# SENSING.net
KiCad netlist of a schematic drawn in Altium Designer
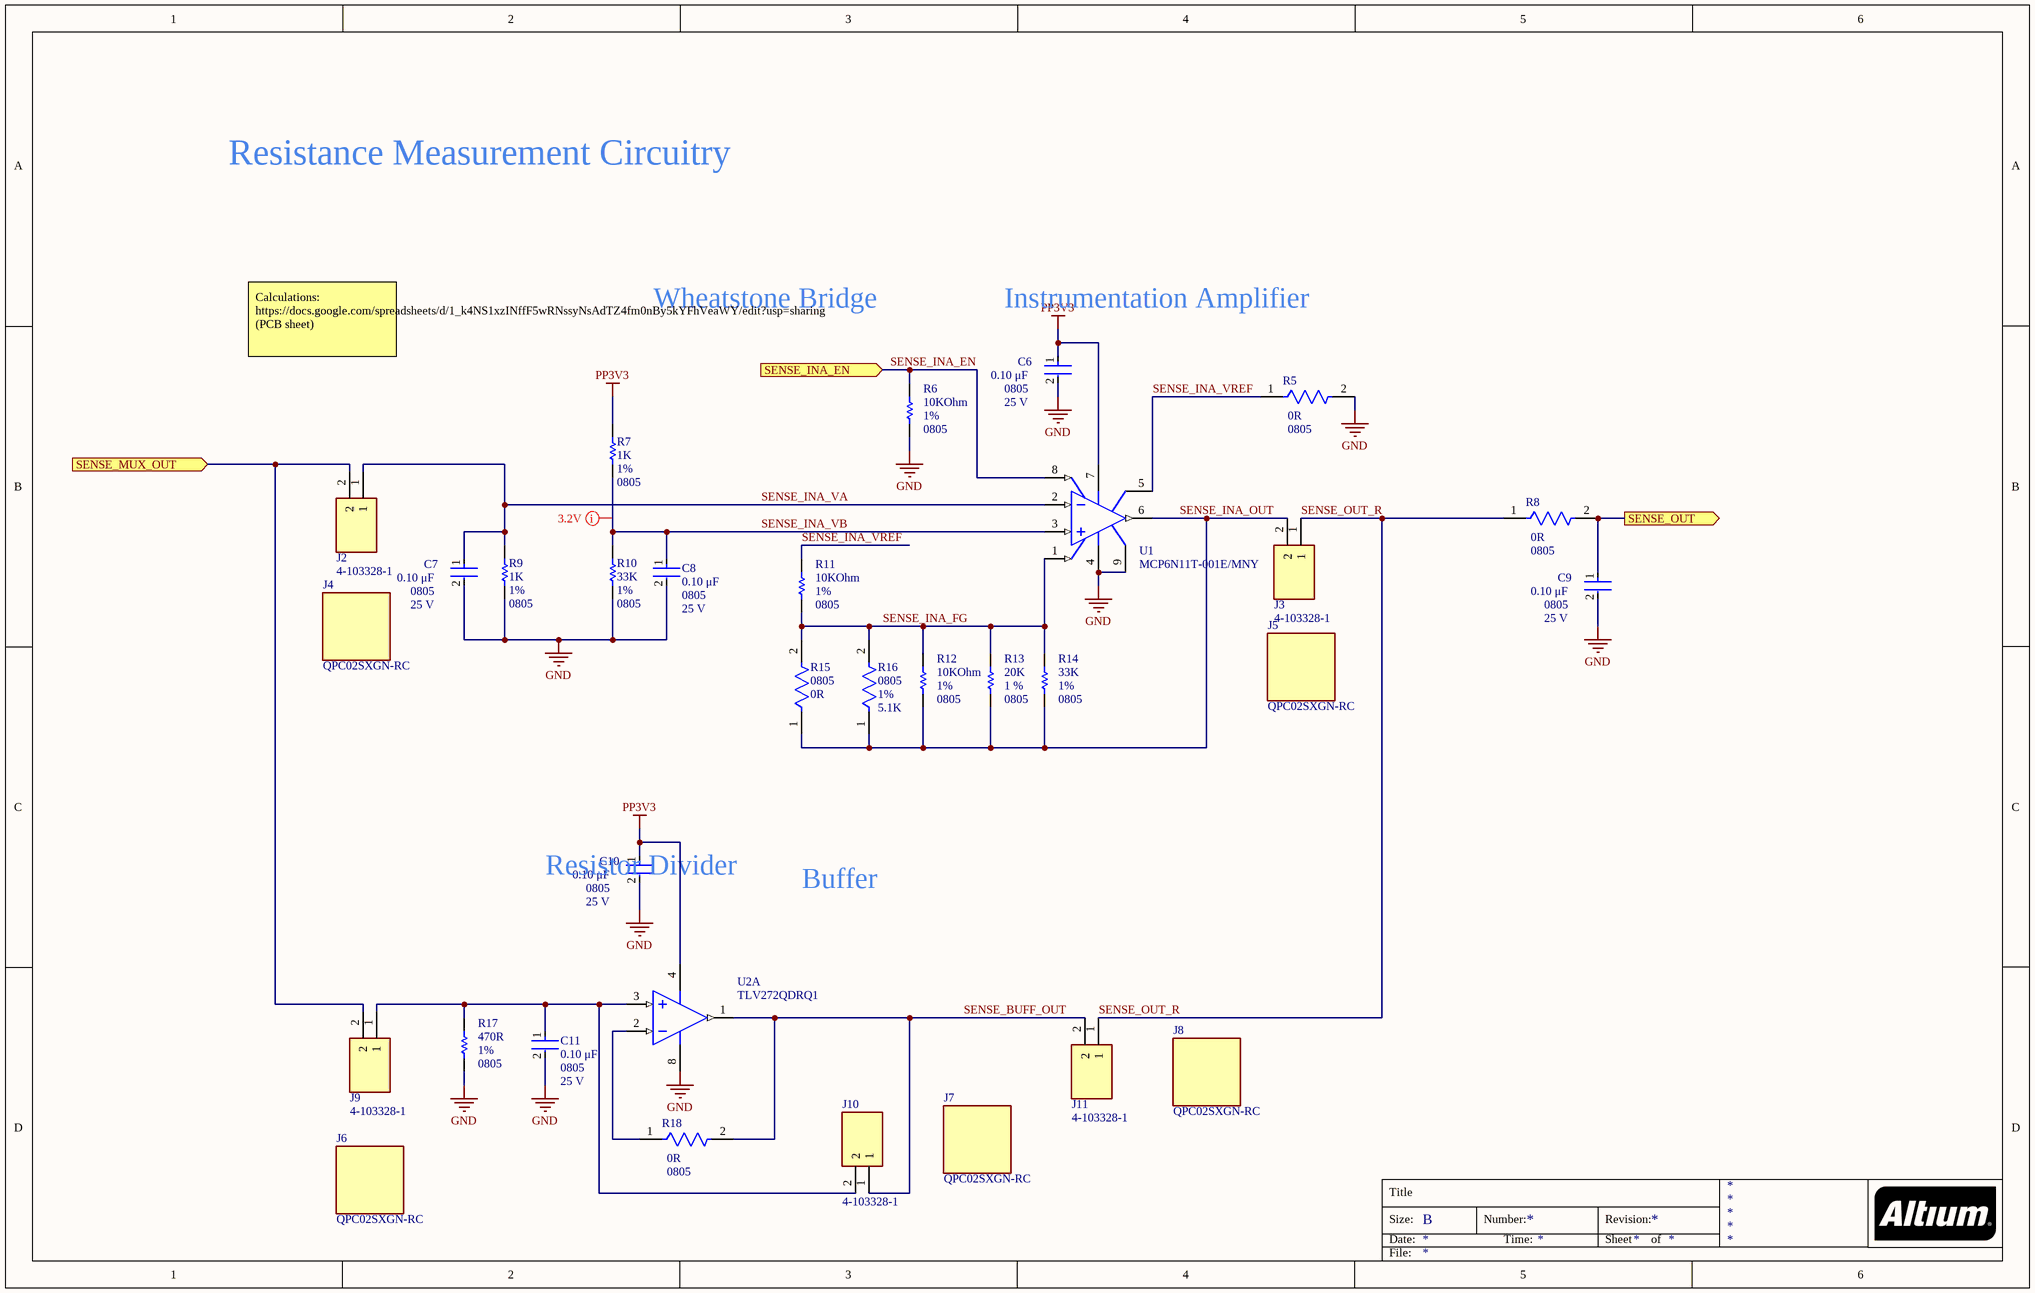
[diagram p0: SENSING.SchDoc]

(export (version "E")
  (design (tool "Eeschema 10.0.6"))
  (components
    (comp (ref "C6")
      (value "C0805C104M3RACTU")
      (footprint "FP-C0805C-DN-MFG")
      (description "CAP CER 0.1UF 25V 20% X7R 0805")
      (fields
        (field (name "CAPACITANCE") "0.10 μF")
        (field (name "PACKAGE") "0805")
        (field (name "TOLERANCE") "0.2")
        (field (name "MANUFACTURER") "KEMET")
        (field (name "VOLTAGE RATING") "25 V")
      )
      (libsource (lib "Altium Content Vault") (part "b4654b650e69147ec39a6b967a45e02"))
    )
    (comp (ref "C7")
      (value "C0805C104M3RACTU")
      (footprint "FP-C0805C-DN-MFG")
      (description "CAP CER 0.1UF 25V 20% X7R 0805")
      (fields
        (field (name "CAPACITANCE") "0.10 μF")
        (field (name "PACKAGE") "0805")
        (field (name "TOLERANCE") "0.2")
        (field (name "MANUFACTURER") "KEMET")
        (field (name "VOLTAGE RATING") "25 V")
      )
      (libsource (lib "Altium Content Vault") (part "b4654b650e69147ec39a6b967a45e02"))
    )
    (comp (ref "C8")
      (value "C0805C104M3RACTU")
      (footprint "FP-C0805C-DN-MFG")
      (description "CAP CER 0.1UF 25V 20% X7R 0805")
      (fields
        (field (name "CAPACITANCE") "0.10 μF")
        (field (name "PACKAGE") "0805")
        (field (name "TOLERANCE") "0.2")
        (field (name "MANUFACTURER") "KEMET")
        (field (name "VOLTAGE RATING") "25 V")
      )
      (libsource (lib "Altium Content Vault") (part "b4654b650e69147ec39a6b967a45e02"))
    )
    (comp (ref "C9")
      (value "C0805C104M3RACTU")
      (footprint "FP-C0805C-DN-MFG")
      (description "CAP CER 0.1UF 25V 20% X7R 0805")
      (fields
        (field (name "CAPACITANCE") "0.10 μF")
        (field (name "PACKAGE") "0805")
        (field (name "TOLERANCE") "0.2")
        (field (name "MANUFACTURER") "KEMET")
        (field (name "VOLTAGE RATING") "25 V")
      )
      (libsource (lib "Altium Content Vault") (part "b4654b650e69147ec39a6b967a45e02"))
    )
    (comp (ref "C10")
      (value "C0805C104M3RACTU")
      (footprint "FP-C0805C-DN-MFG")
      (description "CAP CER 0.1UF 25V 20% X7R 0805")
      (fields
        (field (name "CAPACITANCE") "0.10 μF")
        (field (name "PACKAGE") "0805")
        (field (name "TOLERANCE") "0.2")
        (field (name "MANUFACTURER") "KEMET")
        (field (name "VOLTAGE RATING") "25 V")
      )
      (libsource (lib "Altium Content Vault") (part "b4654b650e69147ec39a6b967a45e02"))
    )
    (comp (ref "C11")
      (value "C0805C104M3RACTU")
      (footprint "FP-C0805C-DN-MFG")
      (description "CAP CER 0.1UF 25V 20% X7R 0805")
      (fields
        (field (name "CAPACITANCE") "0.10 μF")
        (field (name "PACKAGE") "0805")
        (field (name "TOLERANCE") "0.2")
        (field (name "MANUFACTURER") "KEMET")
        (field (name "VOLTAGE RATING") "25 V")
      )
      (libsource (lib "Altium Content Vault") (part "b4654b650e69147ec39a6b967a45e02"))
    )
    (comp (ref "J2")
      (value "4-103328-1")
      (footprint "TE_4-103328-1")
      (description "Connector Header Through Hole 2 position")
      (fields
        (field (name "MF") "TE Connectivity")
        (field (name "MANUFACTURER") "TE Connectivity AMP Connectors")
      )
      (libsource (lib "MLBSchLib") (part "4-103328-1"))
    )
    (comp (ref "J3")
      (value "4-103328-1")
      (footprint "TE_4-103328-1")
      (description "Connector Header Through Hole 2 position")
      (fields
        (field (name "MF") "TE Connectivity")
        (field (name "MANUFACTURER") "TE Connectivity AMP Connectors")
      )
      (libsource (lib "MLBSchLib") (part "4-103328-1"))
    )
    (comp (ref "J4")
      (value "QPC02SXGN-RC")
      (footprint "FP-QPC02SXGN-RC-MFG")
      (description "CONN JUMPER SHORTING .100\" GOLD")
      (fields
        (field (name "MANUFACTURER") "Sullins")
        (field (name "OCTOPART") "https://octopart.com/qpc02sxgn-rc-sullins-19878795")
      )
      (libsource (lib "Altium Content Vault") (part "87292ac8601c6cf2061292f5bede09e"))
    )
    (comp (ref "J5")
      (value "QPC02SXGN-RC")
      (footprint "FP-QPC02SXGN-RC-MFG")
      (description "CONN JUMPER SHORTING .100\" GOLD")
      (fields
        (field (name "MANUFACTURER") "Sullins")
        (field (name "OCTOPART") "https://octopart.com/qpc02sxgn-rc-sullins-19878795")
      )
      (libsource (lib "Altium Content Vault") (part "87292ac8601c6cf2061292f5bede09e"))
    )
    (comp (ref "J6")
      (value "QPC02SXGN-RC")
      (footprint "FP-QPC02SXGN-RC-MFG")
      (description "CONN JUMPER SHORTING .100\" GOLD")
      (fields
        (field (name "MANUFACTURER") "Sullins")
        (field (name "OCTOPART") "https://octopart.com/qpc02sxgn-rc-sullins-19878795")
      )
      (libsource (lib "Altium Content Vault") (part "87292ac8601c6cf2061292f5bede09e"))
    )
    (comp (ref "J7")
      (value "QPC02SXGN-RC")
      (footprint "FP-QPC02SXGN-RC-MFG")
      (description "CONN JUMPER SHORTING .100\" GOLD")
      (fields
        (field (name "MANUFACTURER") "Sullins")
        (field (name "OCTOPART") "https://octopart.com/qpc02sxgn-rc-sullins-19878795")
      )
      (libsource (lib "Altium Content Vault") (part "87292ac8601c6cf2061292f5bede09e"))
    )
    (comp (ref "J8")
      (value "QPC02SXGN-RC")
      (footprint "FP-QPC02SXGN-RC-MFG")
      (description "CONN JUMPER SHORTING .100\" GOLD")
      (fields
        (field (name "MANUFACTURER") "Sullins")
        (field (name "OCTOPART") "https://octopart.com/qpc02sxgn-rc-sullins-19878795")
      )
      (libsource (lib "Altium Content Vault") (part "87292ac8601c6cf2061292f5bede09e"))
    )
    (comp (ref "J9")
      (value "4-103328-1")
      (footprint "TE_4-103328-1")
      (description "Connector Header Through Hole 2 position")
      (fields
        (field (name "MF") "TE Connectivity")
        (field (name "MANUFACTURER") "TE Connectivity AMP Connectors")
      )
      (libsource (lib "MLBSchLib") (part "4-103328-1"))
    )
    (comp (ref "J10")
      (value "4-103328-1")
      (footprint "TE_4-103328-1")
      (description "Connector Header Through Hole 2 position")
      (fields
        (field (name "MF") "TE Connectivity")
        (field (name "MANUFACTURER") "TE Connectivity AMP Connectors")
      )
      (libsource (lib "") (part "4-103328-1_1"))
    )
    (comp (ref "J11")
      (value "4-103328-1")
      (footprint "TE_4-103328-1")
      (description "Connector Header Through Hole 2 position")
      (fields
        (field (name "MF") "TE Connectivity")
        (field (name "MANUFACTURER") "TE Connectivity AMP Connectors")
      )
      (libsource (lib "MLBSchLib") (part "4-103328-1"))
    )
    (comp (ref "R5")
      (value "RMCF0805ZT0R00")
      (footprint "FP-RMCF0805-MFG")
      (description "RES 0 OHM JUMPER 1/8W 0805")
      (fields
        (field (name "CASE/PACKAGE") "0805")
        (field (name "RESISTANCE") "0R")
        (field (name "MANUFACTURER") "Stackpole Electronics Inc")
      )
      (libsource (lib "Altium Content Vault") (part "1029c3af85768c4190bb7ad29bc67b5"))
    )
    (comp (ref "R6")
      (value "10KOhm")
      (footprint "RESC2013X60X35NL10T20")
      (description "Chip Resistor, 10 KOhm, +/- 1%, 0.125 W, -55 to 155 degC, 0805 (2012 Metric), RoHS, Tape and Reel")
      (fields
        (field (name "MANUFACTURER") "Yageo")
        (field (name "PACKAGEREFERENCE") "0805")
        (field (name "MANUFACTURER PART NUMBER") "RC0805FR-0710KL")
        (field (name "TOLERANCE") "1%")
      )
      (libsource (lib "Altium Content Vault") (part "RES-2"))
    )
    (comp (ref "R7")
      (value "RC0805FR-071KL")
      (footprint "RESC2013X60X35ML10T20")
      (description "Chip Resistor, 1 KOhm, +/- 1%, 125 mW, -55 to 155 degC, 0805 (2012 Metric), RoHS, Tape and Reel")
      (fields
        (field (name "RESISTANCE") "1K")
        (field (name "TOLERANCE") "1%")
        (field (name "CASE CODE (IMPERIAL)") "0805")
        (field (name "MANUFACTURER") "Yageo")
      )
      (libsource (lib "Altium Content Vault") (part "RES-2"))
    )
    (comp (ref "R8")
      (value "RMCF0805ZT0R00")
      (footprint "FP-RMCF0805-MFG")
      (description "RES 0 OHM JUMPER 1/8W 0805")
      (fields
        (field (name "CASE/PACKAGE") "0805")
        (field (name "RESISTANCE") "0R")
        (field (name "MANUFACTURER") "Stackpole Electronics Inc")
      )
      (libsource (lib "Altium Content Vault") (part "1029c3af85768c4190bb7ad29bc67b5"))
    )
    (comp (ref "R9")
      (value "RC0805FR-071KL")
      (footprint "RESC2013X60X35ML10T20")
      (description "Chip Resistor, 1 KOhm, +/- 1%, 125 mW, -55 to 155 degC, 0805 (2012 Metric), RoHS, Tape and Reel")
      (fields
        (field (name "RESISTANCE") "1K")
        (field (name "TOLERANCE") "1%")
        (field (name "CASE CODE (IMPERIAL)") "0805")
        (field (name "MANUFACTURER") "Yageo")
      )
      (libsource (lib "Altium Content Vault") (part "RES-2"))
    )
    (comp (ref "R10")
      (value "33K")
      (footprint "RESC2013X70X40LL20T20")
      (fields
        (field (name "PART NUMBER") "ERJ-6GEYJ333V")
        (field (name "MANUFACTURER") "Panasonic")
        (field (name "TOLERANCE") "1%")
        (field (name "PACKAGE") "0805")
      )
      (libsource (lib "Altium Content Vault") (part "RES"))
    )
    (comp (ref "R11")
      (value "10KOhm")
      (footprint "RESC2013X60X35NL10T20")
      (description "Chip Resistor, 10 KOhm, +/- 1%, 0.125 W, -55 to 155 degC, 0805 (2012 Metric), RoHS, Tape and Reel")
      (fields
        (field (name "MANUFACTURER") "Yageo")
        (field (name "PACKAGEREFERENCE") "0805")
        (field (name "MANUFACTURER PART NUMBER") "RC0805FR-0710KL")
        (field (name "TOLERANCE") "1%")
      )
      (libsource (lib "Altium Content Vault") (part "RES-2"))
    )
    (comp (ref "R12")
      (value "10KOhm")
      (footprint "RESC2013X60X35NL10T20")
      (description "Chip Resistor, 10 KOhm, +/- 1%, 0.125 W, -55 to 155 degC, 0805 (2012 Metric), RoHS, Tape and Reel")
      (fields
        (field (name "MANUFACTURER") "Yageo")
        (field (name "PACKAGEREFERENCE") "0805")
        (field (name "MANUFACTURER PART NUMBER") "RC0805FR-0710KL")
        (field (name "TOLERANCE") "1%")
      )
      (libsource (lib "Altium Content Vault") (part "RES-2"))
    )
    (comp (ref "R13")
      (value "20K")
      (footprint "RESC0805(2012)_N")
      (description "20K 0.125W 1% 0805 (2012 Metric)  SMD")
      (fields
        (field (name "POWER") "0.125 W")
        (field (name "TOLERANCE") "1 %")
        (field (name "CASE-EIA") "0805")
        (field (name "MANUFACTURER PART NUMBER") "RC0805FR-0720KL")
      )
      (libsource (lib "Altium Content Vault") (part "RES"))
    )
    (comp (ref "R14")
      (value "33K")
      (footprint "RESC2013X70X40LL20T20")
      (fields
        (field (name "PART NUMBER") "ERJ-6GEYJ333V")
        (field (name "MANUFACTURER") "Panasonic")
        (field (name "TOLERANCE") "1%")
        (field (name "PACKAGE") "0805")
      )
      (libsource (lib "Altium Content Vault") (part "RES"))
    )
    (comp (ref "R15")
      (value "RMCF0805ZT0R00")
      (footprint "FP-RMCF0805-MFG")
      (description "RES 0 OHM JUMPER 1/8W 0805")
      (fields
        (field (name "CASE/PACKAGE") "0805")
        (field (name "RESISTANCE") "0R")
        (field (name "MANUFACTURER") "Stackpole Electronics Inc")
      )
      (libsource (lib "Altium Content Vault") (part "1029c3af85768c4190bb7ad29bc67b5"))
    )
    (comp (ref "R16")
      (value "CRCW08055K10FKEA")
      (footprint "FP-CRCW0805-e3-MFG")
      (description "RES Thick Film, 5.1kΩ, 1%, 0.125W, 100ppm/°C, 0805")
      (fields
        (field (name "CASE CODE (IMPERIAL)") "0805")
        (field (name "TOLERANCE") "1%")
        (field (name "RESISTANCE") "5.1K")
        (field (name "MANUFACTURER") "Vishay Dale")
        (field (name "MANUFACTURER PART NUMBER") "CRCW08055K10FKEAC")
      )
      (libsource (lib "Altium Content Vault") (part "1029c3af85768c4190bb7ad29bc67b5"))
    )
    (comp (ref "R17")
      (value "RC0805FR-07470RL")
      (footprint "RESC2013X60X35LL10T20")
      (description "Chip Resistor, 470 Ohm, +/- 1%, 125 mW, -55 to 155 degC, 0805 (2012 Metric), RoHS, Tape and Reel")
      (fields
        (field (name "MANUFACTURER") "Yageo")
        (field (name "PACKAGE REFERENCE") "0805")
        (field (name "RESISTANCE TOLERANCE") "1%")
        (field (name "RESISTANCE") "470R")
      )
      (libsource (lib "Altium Content Vault") (part "RES-2"))
    )
    (comp (ref "R18")
      (value "RMCF0805ZT0R00")
      (footprint "FP-RMCF0805-MFG")
      (description "RES 0 OHM JUMPER 1/8W 0805")
      (fields
        (field (name "CASE/PACKAGE") "0805")
        (field (name "RESISTANCE") "0R")
        (field (name "MANUFACTURER") "Stackpole Electronics Inc")
      )
      (libsource (lib "Altium Content Vault") (part "1029c3af85768c4190bb7ad29bc67b5"))
    )
    (comp (ref "U1")
      (value "MCP6N11T-001E/MNY")
      (footprint "TDFN-MN8")
      (description "None")
      (fields (field (name "MANUFACTURER") "Microchip Technology"))
      (libsource (lib "Altium Content Vault") (part "AMP-INA-MCP6N11-TDFN9"))
    )
    (comp (ref "U2")
      (value "TLV272QDRQ1")
      (footprint "D0008A_N")
      (fields (field (name "MANUFACTURER") "Texas Instruments"))
      (libsource (lib "Altium Content Vault") (part "TI-TLV_TLC-8"))
    )
  )
  (nets
    (net (code "1") (name "/SENSE_BUFF_OUT") (class "Default")
      (node (ref "J10") (pin "1") (pinfunction "1_1") (pintype "passive"))
      (node (ref "J11") (pin "2") (pinfunction "2_2") (pintype "passive"))
      (node (ref "R18") (pin "2") (pinfunction "2_2") (pintype "passive"))
      (node (ref "U2") (pin "1") (pinfunction "OUT1_1") (pintype "output"))
    )
    (net (code "2") (name "/SENSE_INA_EN") (class "Default")
      (node (ref "R6") (pin "2") (pinfunction "2_2") (pintype "passive"))
      (node (ref "U1") (pin "8") (pinfunction "EN/~{CAL}_8") (pintype "input"))
    )
    (net (code "3") (name "/SENSE_INA_FG") (class "Default")
      (node (ref "R11") (pin "1") (pinfunction "1_1") (pintype "passive"))
      (node (ref "R12") (pin "2") (pinfunction "2_2") (pintype "passive"))
      (node (ref "R13") (pin "2") (pinfunction "2_2") (pintype "passive"))
      (node (ref "R14") (pin "2") (pinfunction "2_2") (pintype "passive"))
      (node (ref "R15") (pin "2") (pinfunction "2_2") (pintype "passive"))
      (node (ref "R16") (pin "2") (pinfunction "2_2") (pintype "passive"))
      (node (ref "U1") (pin "1") (pinfunction "VFG_1") (pintype "input"))
    )
    (net (code "4") (name "/SENSE_INA_OUT") (class "Default")
      (node (ref "J3") (pin "2") (pinfunction "2_2") (pintype "passive"))
      (node (ref "R12") (pin "1") (pinfunction "1_1") (pintype "passive"))
      (node (ref "R13") (pin "1") (pinfunction "1_1") (pintype "passive"))
      (node (ref "R14") (pin "1") (pinfunction "1_1") (pintype "passive"))
      (node (ref "R15") (pin "1") (pinfunction "1_1") (pintype "passive"))
      (node (ref "R16") (pin "1") (pinfunction "1_1") (pintype "passive"))
      (node (ref "U1") (pin "6") (pinfunction "VOUT_6") (pintype "output"))
    )
    (net (code "5") (name "/SENSE_INA_VA") (class "Default")
      (node (ref "C7") (pin "1") (pinfunction "1_1") (pintype "passive"))
      (node (ref "J2") (pin "1") (pinfunction "1_1") (pintype "passive"))
      (node (ref "R9") (pin "2") (pinfunction "2_2") (pintype "passive"))
      (node (ref "U1") (pin "2") (pinfunction "VIM_2") (pintype "input"))
    )
    (net (code "6") (name "/SENSE_INA_VB") (class "Default")
      (node (ref "C8") (pin "1") (pinfunction "1_1") (pintype "passive"))
      (node (ref "R10") (pin "2") (pinfunction "2_2") (pintype "passive"))
      (node (ref "R7") (pin "1") (pinfunction "1_1") (pintype "passive"))
      (node (ref "U1") (pin "3") (pinfunction "VIP_3") (pintype "input"))
    )
    (net (code "7") (name "/SENSE_INA_VREF") (class "Default")
      (node (ref "R11") (pin "2") (pinfunction "2_2") (pintype "passive"))
      (node (ref "R5") (pin "1") (pinfunction "1_1") (pintype "passive"))
      (node (ref "U1") (pin "5") (pinfunction "VREF_5") (pintype "power_in"))
    )
    (net (code "8") (name "/SENSE_MUX_OUT") (class "Default")
      (node (ref "J2") (pin "2") (pinfunction "2_2") (pintype "passive"))
      (node (ref "J9") (pin "2") (pinfunction "2_2") (pintype "passive"))
    )
    (net (code "9") (name "/SENSE_OUT") (class "Default")
      (node (ref "C9") (pin "1") (pinfunction "1_1") (pintype "passive"))
      (node (ref "R8") (pin "2") (pinfunction "2_2") (pintype "passive"))
    )
    (net (code "10") (name "/SENSE_OUT_R") (class "Default")
      (node (ref "J11") (pin "1") (pinfunction "1_1") (pintype "passive"))
      (node (ref "J3") (pin "1") (pinfunction "1_1") (pintype "passive"))
      (node (ref "R8") (pin "1") (pinfunction "1_1") (pintype "passive"))
    )
    (net (code "11") (name "GND") (class "Default")
      (node (ref "C10") (pin "2") (pinfunction "2_2") (pintype "passive"))
      (node (ref "C11") (pin "2") (pinfunction "2_2") (pintype "passive"))
      (node (ref "C6") (pin "2") (pinfunction "2_2") (pintype "passive"))
      (node (ref "C7") (pin "2") (pinfunction "2_2") (pintype "passive"))
      (node (ref "C8") (pin "2") (pinfunction "2_2") (pintype "passive"))
      (node (ref "C9") (pin "2") (pinfunction "2_2") (pintype "passive"))
      (node (ref "R10") (pin "1") (pinfunction "1_1") (pintype "passive"))
      (node (ref "R17") (pin "1") (pinfunction "1_1") (pintype "passive"))
      (node (ref "R5") (pin "2") (pinfunction "2_2") (pintype "passive"))
      (node (ref "R6") (pin "1") (pinfunction "1_1") (pintype "passive"))
      (node (ref "R9") (pin "1") (pinfunction "1_1") (pintype "passive"))
      (node (ref "U1") (pin "4") (pinfunction "VSS_4") (pintype "power_in"))
      (node (ref "U1") (pin "9") (pinfunction "EP_9") (pintype "power_in"))
      (node (ref "U2") (pin "8") (pinfunction "VDD_8") (pintype "power_in"))
    )
    (net (code "12") (name "Net-(U2A-IN1+)") (class "Default")
      (node (ref "C11") (pin "1") (pinfunction "1_1") (pintype "passive"))
      (node (ref "J10") (pin "2") (pinfunction "2_2") (pintype "passive"))
      (node (ref "J9") (pin "1") (pinfunction "1_1") (pintype "passive"))
      (node (ref "R17") (pin "2") (pinfunction "2_2") (pintype "passive"))
      (node (ref "U2") (pin "3") (pinfunction "IN1+_3") (pintype "input"))
    )
    (net (code "13") (name "Net-(U2A-IN1-)") (class "Default")
      (node (ref "R18") (pin "1") (pinfunction "1_1") (pintype "passive"))
      (node (ref "U2") (pin "2") (pinfunction "IN1-_2") (pintype "input"))
    )
    (net (code "14") (name "PP3V3") (class "Default")
      (node (ref "C10") (pin "1") (pinfunction "1_1") (pintype "passive"))
      (node (ref "C6") (pin "1") (pinfunction "1_1") (pintype "passive"))
      (node (ref "R7") (pin "2") (pinfunction "2_2") (pintype "passive"))
      (node (ref "U1") (pin "7") (pinfunction "VDD_7") (pintype "power_in"))
      (node (ref "U2") (pin "4") (pinfunction "GND_4") (pintype "power_in"))
    )
  )
)
